# tACS_precision_revised.net
KiCad netlist of a schematic drawn in EAGLE
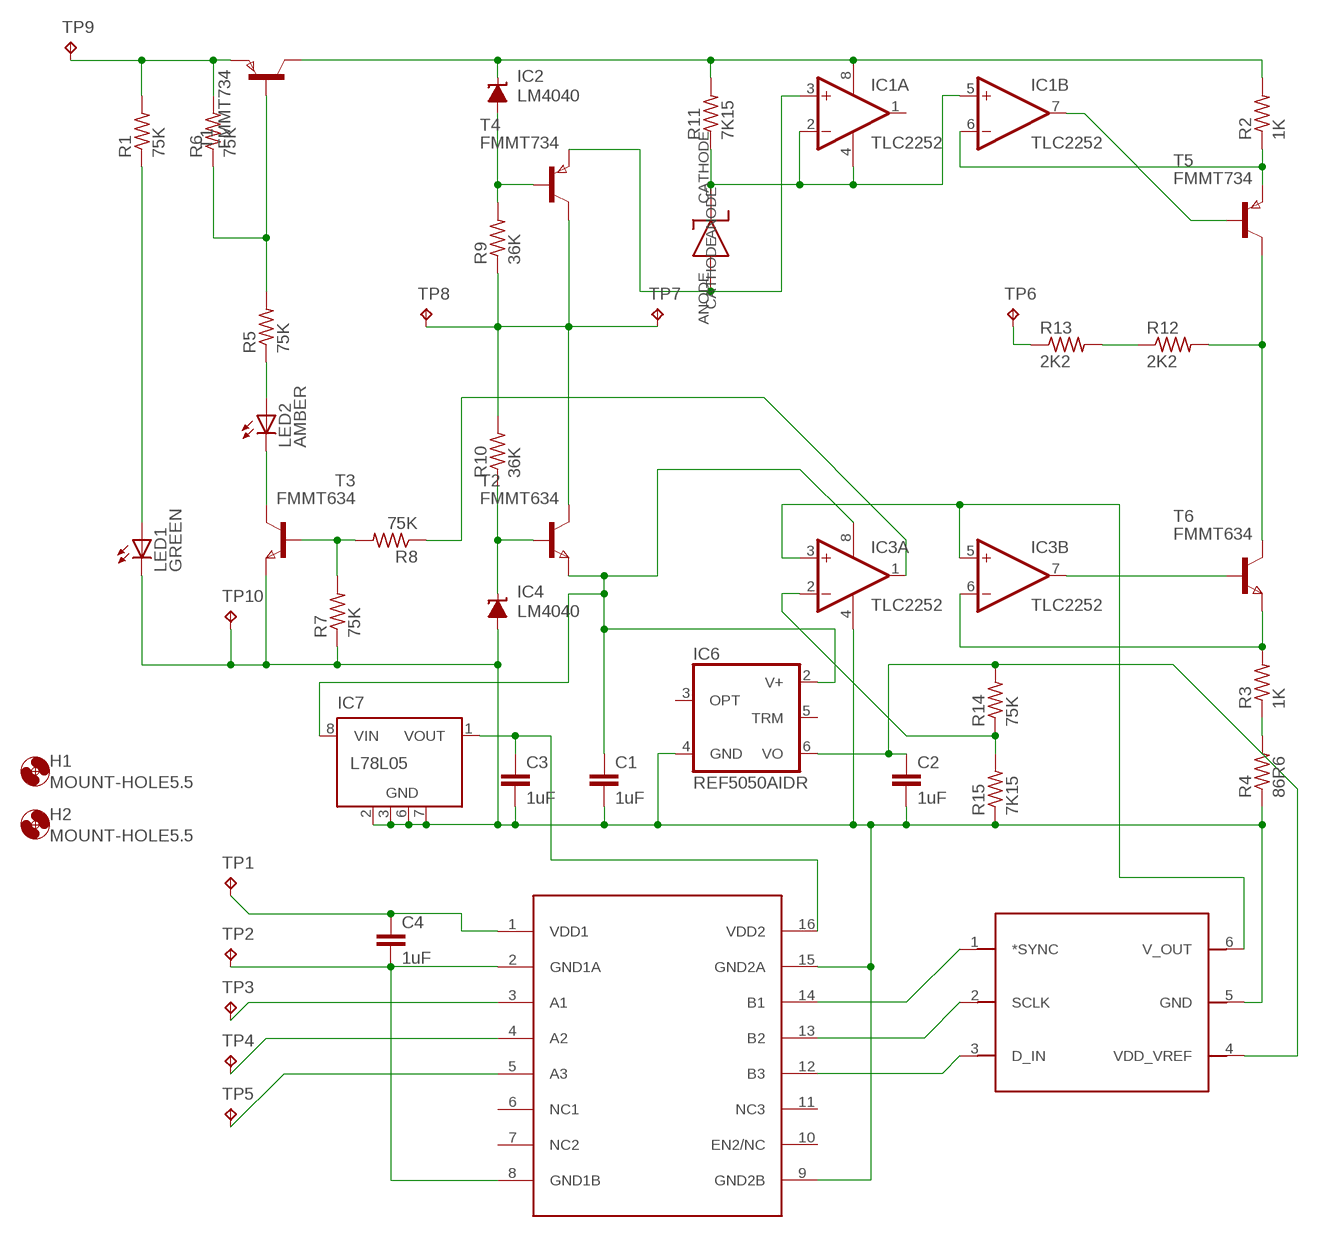
[diagram p0: schematic, sheet 1]

(export (version "E")
  (design (tool "Eeschema 10.0.6"))
  (components
    (comp (ref "C1")
      (value "1uF")
      (footprint "eagle-import:C1608")
      (libsource (lib "eagle-import") (part "C-EUC1608"))
    )
    (comp (ref "C2")
      (value "1uF")
      (footprint "eagle-import:C1608")
      (libsource (lib "eagle-import") (part "C-EUC1608"))
    )
    (comp (ref "C3")
      (value "1uF")
      (footprint "eagle-import:C1608")
      (libsource (lib "eagle-import") (part "C-EUC1608"))
    )
    (comp (ref "C4")
      (value "1uF")
      (footprint "eagle-import:C1608")
      (libsource (lib "eagle-import") (part "C-EUC1608"))
    )
    (comp (ref "H1")
      (value "MOUNT-HOLE5.5")
      (footprint "eagle-import:5,5")
      (libsource (lib "eagle-import") (part "MOUNT-HOLE5.5"))
    )
    (comp (ref "H2")
      (value "MOUNT-HOLE5.5")
      (footprint "eagle-import:5,5")
      (libsource (lib "eagle-import") (part "MOUNT-HOLE5.5"))
    )
    (comp (ref "IC1")
      (value "TLC2252")
      (footprint "eagle-import:SO08")
      (libsource (lib "eagle-import") (part "TLC272D"))
    )
    (comp (ref "IC2")
      (value "LM4040")
      (footprint "eagle-import:DBZ_R-PDSO-G3")
      (fields (field (name "MPN") "LM4041A12IDBZR"))
      (libsource (lib "eagle-import") (part "LM4041DBZA12"))
    )
    (comp (ref "IC3")
      (value "TLC2252")
      (footprint "eagle-import:SO08")
      (libsource (lib "eagle-import") (part "TLC272D"))
    )
    (comp (ref "IC4")
      (value "LM4040")
      (footprint "eagle-import:DBZ_R-PDSO-G3")
      (fields (field (name "MPN") "LM4041A12IDBZR"))
      (libsource (lib "eagle-import") (part "LM4041DBZA12"))
    )
    (comp (ref "IC6")
      (value "REF5050AIDR")
      (footprint "eagle-import:SO08")
      (libsource (lib "eagle-import") (part "REF03D"))
    )
    (comp (ref "IC7")
      (value "L78L05")
      (footprint "eagle-import:SO08")
      (libsource (lib "eagle-import") (part "78LSMD05"))
    )
    (comp (ref "LED1")
      (value "GREEN")
      (footprint "eagle-import:SML0603")
      (libsource (lib "eagle-import") (part "LEDSML0603"))
    )
    (comp (ref "LED2")
      (value "AMBER")
      (footprint "eagle-import:SML1206")
      (libsource (lib "eagle-import") (part "LEDSML1206"))
    )
    (comp (ref "R1")
      (value "75K")
      (footprint "eagle-import:R0603")
      (libsource (lib "eagle-import") (part "R-US_R0603"))
    )
    (comp (ref "R2")
      (value "1K")
      (footprint "eagle-import:R0603")
      (libsource (lib "eagle-import") (part "R-US_R0603"))
    )
    (comp (ref "R3")
      (value "1K")
      (footprint "eagle-import:R0603")
      (libsource (lib "eagle-import") (part "R-US_R0603"))
    )
    (comp (ref "R4")
      (value "86R6")
      (footprint "eagle-import:R0603")
      (libsource (lib "eagle-import") (part "R-US_R0603"))
    )
    (comp (ref "R5")
      (value "75K")
      (footprint "eagle-import:R0603")
      (libsource (lib "eagle-import") (part "R-US_R0603"))
    )
    (comp (ref "R6")
      (value "75K")
      (footprint "eagle-import:R0603")
      (libsource (lib "eagle-import") (part "R-US_R0603"))
    )
    (comp (ref "R7")
      (value "75K")
      (footprint "eagle-import:R0603")
      (libsource (lib "eagle-import") (part "R-US_R0603"))
    )
    (comp (ref "R8")
      (value "75K")
      (footprint "eagle-import:R0603")
      (libsource (lib "eagle-import") (part "R-US_R0603"))
    )
    (comp (ref "R9")
      (value "36K")
      (footprint "eagle-import:R0603")
      (libsource (lib "eagle-import") (part "R-US_R0603"))
    )
    (comp (ref "R10")
      (value "36K")
      (footprint "eagle-import:R0603")
      (libsource (lib "eagle-import") (part "R-US_R0603"))
    )
    (comp (ref "R11")
      (value "7K15")
      (footprint "eagle-import:R0603")
      (libsource (lib "eagle-import") (part "R-US_R0603"))
    )
    (comp (ref "R12")
      (value "2K2")
      (footprint "eagle-import:R2512")
      (libsource (lib "eagle-import") (part "R-US_R2512"))
    )
    (comp (ref "R13")
      (value "2K2")
      (footprint "eagle-import:R2512")
      (libsource (lib "eagle-import") (part "R-US_R2512"))
    )
    (comp (ref "R14")
      (value "75K")
      (footprint "eagle-import:R0603")
      (libsource (lib "eagle-import") (part "R-US_R0603"))
    )
    (comp (ref "R15")
      (value "7K15")
      (footprint "eagle-import:R0603")
      (libsource (lib "eagle-import") (part "R-US_R0603"))
    )
    (comp (ref "T1")
      (value "FMMT734")
      (footprint "eagle-import:SOT-23")
      (fields (field (name "MPN") "FMMT720"))
      (libsource (lib "eagle-import") (part "FMMT720"))
    )
    (comp (ref "T2")
      (value "FMMT634")
      (footprint "eagle-import:SOT-23")
      (fields (field (name "MPN") "FMMT619"))
      (libsource (lib "eagle-import") (part "FMMT624"))
    )
    (comp (ref "T3")
      (value "FMMT634")
      (footprint "eagle-import:SOT-23")
      (fields (field (name "MPN") "FMMT619"))
      (libsource (lib "eagle-import") (part "FMMT624"))
    )
    (comp (ref "T4")
      (value "FMMT734")
      (footprint "eagle-import:SOT-23")
      (fields (field (name "MPN") "FMMT720"))
      (libsource (lib "eagle-import") (part "FMMT720"))
    )
    (comp (ref "T5")
      (value "FMMT734")
      (footprint "eagle-import:SOT-23")
      (fields (field (name "MPN") "FMMT720"))
      (libsource (lib "eagle-import") (part "FMMT720"))
    )
    (comp (ref "T6")
      (value "FMMT634")
      (footprint "eagle-import:SOT-23")
      (fields (field (name "MPN") "FMMT619"))
      (libsource (lib "eagle-import") (part "FMMT624"))
    )
    (comp (ref "TP1")
      (value "TPPAD1-13Y")
      (footprint "eagle-import:P1-13Y")
      (libsource (lib "eagle-import") (part "TPPAD1-13Y"))
    )
    (comp (ref "TP2")
      (value "TPPAD1-13Y")
      (footprint "eagle-import:P1-13Y")
      (libsource (lib "eagle-import") (part "TPPAD1-13Y"))
    )
    (comp (ref "TP3")
      (value "TPPAD1-13Y")
      (footprint "eagle-import:P1-13Y")
      (libsource (lib "eagle-import") (part "TPPAD1-13Y"))
    )
    (comp (ref "TP4")
      (value "TPPAD1-13Y")
      (footprint "eagle-import:P1-13Y")
      (libsource (lib "eagle-import") (part "TPPAD1-13Y"))
    )
    (comp (ref "TP5")
      (value "TPPAD1-13Y")
      (footprint "eagle-import:P1-13Y")
      (libsource (lib "eagle-import") (part "TPPAD1-13Y"))
    )
    (comp (ref "TP6")
      (value "TPPAD1-13Y")
      (footprint "eagle-import:P1-13Y")
      (libsource (lib "eagle-import") (part "TPPAD1-13Y"))
    )
    (comp (ref "TP7")
      (value "TPPAD1-13Y")
      (footprint "eagle-import:P1-13Y")
      (libsource (lib "eagle-import") (part "TPPAD1-13Y"))
    )
    (comp (ref "TP8")
      (value "TPPAD1-13Y")
      (footprint "eagle-import:P1-13Y")
      (libsource (lib "eagle-import") (part "TPPAD1-13Y"))
    )
    (comp (ref "TP9")
      (value "TPPAD1-13Y")
      (footprint "eagle-import:P1-13Y")
      (libsource (lib "eagle-import") (part "TPPAD1-13Y"))
    )
    (comp (ref "TP10")
      (value "TPPAD1-13Y")
      (footprint "eagle-import:P1-13Y")
      (libsource (lib "eagle-import") (part "TPPAD1-13Y"))
    )
    (comp (ref "U$1")
      (value "DAC7311")
      (footprint "eagle-import:SC70-6")
      (libsource (lib "eagle-import") (part "DAC7311"))
    )
    (comp (ref "U$2")
      (value "SI8630BD")
      (footprint "eagle-import:SOIC16R")
      (libsource (lib "eagle-import") (part "SI8630BD-B-IS"))
    )
    (comp (ref "U$3")
      (value "ADR5041")
      (footprint "eagle-import:SC70-3")
      (libsource (lib "eagle-import") (part "ADR5041BKSZ"))
    )
  )
  (nets
    (net (code "1") (name "Net-(IC1A-+IN)") (class "Default")
      (node (ref "IC1") (pin "3") (pinfunction "+IN_3") (pintype "input"))
      (node (ref "T4") (pin "2") (pinfunction "E_2") (pintype "passive"))
      (node (ref "U$3") (pin "ANODE") (pinfunction "ANODE_ANODE") (pintype "bidirectional"))
    )
    (net (code "2") (name "Net-(IC1A--IN)") (class "Default")
      (node (ref "IC1") (pin "2") (pinfunction "-IN_2") (pintype "input"))
      (node (ref "IC1") (pin "4") (pinfunction "V-_4") (pintype "power_in"))
      (node (ref "IC1") (pin "5") (pinfunction "+IN_5") (pintype "input"))
      (node (ref "R11") (pin "1") (pinfunction "1_1") (pintype "passive"))
      (node (ref "U$3") (pin "CATHODE") (pinfunction "CATHODE_CATHODE") (pintype "bidirectional"))
    )
    (net (code "3") (name "Net-(IC1B--IN)") (class "Default")
      (node (ref "IC1") (pin "6") (pinfunction "-IN_6") (pintype "input"))
      (node (ref "R2") (pin "1") (pinfunction "1_1") (pintype "passive"))
      (node (ref "T5") (pin "2") (pinfunction "E_2") (pintype "passive"))
    )
    (net (code "4") (name "Net-(IC1B-OUT)") (class "Default")
      (node (ref "IC1") (pin "7") (pinfunction "OUT_7") (pintype "output"))
      (node (ref "T5") (pin "3") (pinfunction "B_3") (pintype "passive"))
    )
    (net (code "5") (name "Net-(IC1C-V+)") (class "Default")
      (node (ref "IC1") (pin "8") (pinfunction "V+_8") (pintype "power_in"))
      (node (ref "IC2") (pin "1") (pinfunction "C_1") (pintype "passive"))
      (node (ref "R11") (pin "2") (pinfunction "2_2") (pintype "passive"))
      (node (ref "R2") (pin "2") (pinfunction "2_2") (pintype "passive"))
      (node (ref "T1") (pin "1") (pinfunction "C_1") (pintype "passive"))
    )
    (net (code "6") (name "Net-(IC2-A)") (class "Default")
      (node (ref "IC2") (pin "2") (pinfunction "A_2") (pintype "passive"))
      (node (ref "R9") (pin "2") (pinfunction "2_2") (pintype "passive"))
      (node (ref "T4") (pin "3") (pinfunction "B_3") (pintype "passive"))
    )
    (net (code "7") (name "Net-(IC3A-+IN)") (class "Default")
      (node (ref "IC3") (pin "3") (pinfunction "+IN_3") (pintype "input"))
      (node (ref "IC3") (pin "5") (pinfunction "+IN_5") (pintype "input"))
      (node (ref "U$1") (pin "6") (pinfunction "V_OUT_6") (pintype "bidirectional"))
    )
    (net (code "8") (name "Net-(IC3A--IN)") (class "Default")
      (node (ref "IC3") (pin "2") (pinfunction "-IN_2") (pintype "input"))
      (node (ref "R14") (pin "1") (pinfunction "1_1") (pintype "passive"))
      (node (ref "R15") (pin "2") (pinfunction "2_2") (pintype "passive"))
    )
    (net (code "9") (name "Net-(IC3A-OUT)") (class "Default")
      (node (ref "IC3") (pin "1") (pinfunction "OUT_1") (pintype "output"))
      (node (ref "R8") (pin "1") (pinfunction "1_1") (pintype "passive"))
    )
    (net (code "10") (name "Net-(IC3B--IN)") (class "Default")
      (node (ref "IC3") (pin "6") (pinfunction "-IN_6") (pintype "input"))
      (node (ref "R3") (pin "2") (pinfunction "2_2") (pintype "passive"))
      (node (ref "T6") (pin "2") (pinfunction "E_2") (pintype "passive"))
    )
    (net (code "11") (name "Net-(IC3B-OUT)") (class "Default")
      (node (ref "IC3") (pin "7") (pinfunction "OUT_7") (pintype "output"))
      (node (ref "T6") (pin "3") (pinfunction "B_3") (pintype "passive"))
    )
    (net (code "12") (name "Net-(IC3C-V+)") (class "Default")
      (node (ref "C1") (pin "1") (pinfunction "1_1") (pintype "passive"))
      (node (ref "IC3") (pin "8") (pinfunction "V+_8") (pintype "power_in"))
      (node (ref "IC6") (pin "2") (pinfunction "V+_2") (pintype "power_in"))
      (node (ref "IC7") (pin "8") (pinfunction "VIN_8") (pintype "passive"))
      (node (ref "T2") (pin "2") (pinfunction "E_2") (pintype "passive"))
    )
    (net (code "13") (name "Net-(IC3C-V-)") (class "Default")
      (node (ref "C1") (pin "2") (pinfunction "2_2") (pintype "passive"))
      (node (ref "C2") (pin "2") (pinfunction "2_2") (pintype "passive"))
      (node (ref "C3") (pin "2") (pinfunction "2_2") (pintype "passive"))
      (node (ref "IC3") (pin "4") (pinfunction "V-_4") (pintype "power_in"))
      (node (ref "IC4") (pin "2") (pinfunction "A_2") (pintype "passive"))
      (node (ref "IC6") (pin "4") (pinfunction "GND_4") (pintype "power_in"))
      (node (ref "IC7") (pin "2") (pinfunction "GND_2") (pintype "power_in"))
      (node (ref "IC7") (pin "3") (pinfunction "GND_3") (pintype "power_in"))
      (node (ref "IC7") (pin "6") (pinfunction "GND_6") (pintype "power_in"))
      (node (ref "IC7") (pin "7") (pinfunction "GND_7") (pintype "power_in"))
      (node (ref "LED1") (pin "C") (pinfunction "C_C") (pintype "passive"))
      (node (ref "R15") (pin "1") (pinfunction "1_1") (pintype "passive"))
      (node (ref "R4") (pin "1") (pinfunction "1_1") (pintype "passive"))
      (node (ref "R7") (pin "1") (pinfunction "1_1") (pintype "passive"))
      (node (ref "T3") (pin "2") (pinfunction "E_2") (pintype "passive"))
      (node (ref "TP10") (pin "TP") (pinfunction "TP_TP") (pintype "input"))
      (node (ref "U$1") (pin "5") (pinfunction "GND_5") (pintype "bidirectional"))
      (node (ref "U$2") (pin "15") (pinfunction "GND2A_15") (pintype "bidirectional"))
      (node (ref "U$2") (pin "9") (pinfunction "GND2B_9") (pintype "bidirectional"))
    )
    (net (code "14") (name "Net-(IC4-C)") (class "Default")
      (node (ref "IC4") (pin "1") (pinfunction "C_1") (pintype "passive"))
      (node (ref "R10") (pin "1") (pinfunction "1_1") (pintype "passive"))
      (node (ref "T2") (pin "3") (pinfunction "B_3") (pintype "passive"))
    )
    (net (code "15") (name "Net-(IC6-VO)") (class "Default")
      (node (ref "C2") (pin "1") (pinfunction "1_1") (pintype "passive"))
      (node (ref "IC6") (pin "6") (pinfunction "VO_6") (pintype "output"))
      (node (ref "R14") (pin "2") (pinfunction "2_2") (pintype "passive"))
      (node (ref "U$1") (pin "4") (pinfunction "VDD_VREF_4") (pintype "bidirectional"))
    )
    (net (code "16") (name "Net-(IC7A-VOUT)") (class "Default")
      (node (ref "C3") (pin "1") (pinfunction "1_1") (pintype "passive"))
      (node (ref "IC7") (pin "1") (pinfunction "VOUT_1") (pintype "output"))
      (node (ref "U$2") (pin "16") (pinfunction "VDD2_16") (pintype "bidirectional"))
    )
    (net (code "17") (name "Net-(LED1-PadA)") (class "Default")
      (node (ref "LED1") (pin "A") (pinfunction "A_A") (pintype "passive"))
      (node (ref "R1") (pin "1") (pinfunction "1_1") (pintype "passive"))
    )
    (net (code "18") (name "Net-(LED2-PadA)") (class "Default")
      (node (ref "LED2") (pin "A") (pinfunction "A_A") (pintype "passive"))
      (node (ref "R5") (pin "1") (pinfunction "1_1") (pintype "passive"))
    )
    (net (code "19") (name "Net-(R3-Pad1)") (class "Default")
      (node (ref "R3") (pin "1") (pinfunction "1_1") (pintype "passive"))
      (node (ref "R4") (pin "2") (pinfunction "2_2") (pintype "passive"))
    )
    (net (code "20") (name "Net-(R12-Pad1)") (class "Default")
      (node (ref "R12") (pin "1") (pinfunction "1_1") (pintype "passive"))
      (node (ref "R13") (pin "2") (pinfunction "2_2") (pintype "passive"))
    )
    (net (code "21") (name "Net-(R13-Pad1)") (class "Default")
      (node (ref "R13") (pin "1") (pinfunction "1_1") (pintype "passive"))
      (node (ref "TP6") (pin "TP") (pinfunction "TP_TP") (pintype "input"))
    )
    (net (code "22") (name "Net-(T1-B)") (class "Default")
      (node (ref "R5") (pin "2") (pinfunction "2_2") (pintype "passive"))
      (node (ref "R6") (pin "1") (pinfunction "1_1") (pintype "passive"))
      (node (ref "T1") (pin "3") (pinfunction "B_3") (pintype "passive"))
    )
    (net (code "23") (name "Net-(T1-E)") (class "Default")
      (node (ref "R1") (pin "2") (pinfunction "2_2") (pintype "passive"))
      (node (ref "R6") (pin "2") (pinfunction "2_2") (pintype "passive"))
      (node (ref "T1") (pin "2") (pinfunction "E_2") (pintype "passive"))
      (node (ref "TP9") (pin "TP") (pinfunction "TP_TP") (pintype "input"))
    )
    (net (code "24") (name "Net-(T2-C)") (class "Default")
      (node (ref "R10") (pin "2") (pinfunction "2_2") (pintype "passive"))
      (node (ref "R9") (pin "1") (pinfunction "1_1") (pintype "passive"))
      (node (ref "T2") (pin "1") (pinfunction "C_1") (pintype "passive"))
      (node (ref "T4") (pin "1") (pinfunction "C_1") (pintype "passive"))
      (node (ref "TP7") (pin "TP") (pinfunction "TP_TP") (pintype "input"))
      (node (ref "TP8") (pin "TP") (pinfunction "TP_TP") (pintype "input"))
    )
    (net (code "25") (name "Net-(T3-B)") (class "Default")
      (node (ref "R7") (pin "2") (pinfunction "2_2") (pintype "passive"))
      (node (ref "R8") (pin "2") (pinfunction "2_2") (pintype "passive"))
      (node (ref "T3") (pin "3") (pinfunction "B_3") (pintype "passive"))
    )
    (net (code "26") (name "Net-(T3-C)") (class "Default")
      (node (ref "LED2") (pin "C") (pinfunction "C_C") (pintype "passive"))
      (node (ref "T3") (pin "1") (pinfunction "C_1") (pintype "passive"))
    )
    (net (code "27") (name "Net-(T5-C)") (class "Default")
      (node (ref "R12") (pin "2") (pinfunction "2_2") (pintype "passive"))
      (node (ref "T5") (pin "1") (pinfunction "C_1") (pintype "passive"))
      (node (ref "T6") (pin "1") (pinfunction "C_1") (pintype "passive"))
    )
    (net (code "28") (name "Net-(U$1-*SYNC)") (class "Default")
      (node (ref "U$1") (pin "1") (pinfunction "*SYNC_1") (pintype "bidirectional"))
      (node (ref "U$2") (pin "14") (pinfunction "B1_14") (pintype "bidirectional"))
    )
    (net (code "29") (name "Net-(U$1-D_IN)") (class "Default")
      (node (ref "U$1") (pin "3") (pinfunction "D_IN_3") (pintype "bidirectional"))
      (node (ref "U$2") (pin "12") (pinfunction "B3_12") (pintype "bidirectional"))
    )
    (net (code "30") (name "Net-(U$1-SCLK)") (class "Default")
      (node (ref "U$1") (pin "2") (pinfunction "SCLK_2") (pintype "bidirectional"))
      (node (ref "U$2") (pin "13") (pinfunction "B2_13") (pintype "bidirectional"))
    )
    (net (code "31") (name "Net-(U$2-A1)") (class "Default")
      (node (ref "TP3") (pin "TP") (pinfunction "TP_TP") (pintype "input"))
      (node (ref "U$2") (pin "3") (pinfunction "A1_3") (pintype "bidirectional"))
    )
    (net (code "32") (name "Net-(U$2-A2)") (class "Default")
      (node (ref "TP4") (pin "TP") (pinfunction "TP_TP") (pintype "input"))
      (node (ref "U$2") (pin "4") (pinfunction "A2_4") (pintype "bidirectional"))
    )
    (net (code "33") (name "Net-(U$2-A3)") (class "Default")
      (node (ref "TP5") (pin "TP") (pinfunction "TP_TP") (pintype "input"))
      (node (ref "U$2") (pin "5") (pinfunction "A3_5") (pintype "bidirectional"))
    )
    (net (code "34") (name "Net-(U$2-GND1A)") (class "Default")
      (node (ref "C4") (pin "2") (pinfunction "2_2") (pintype "passive"))
      (node (ref "TP2") (pin "TP") (pinfunction "TP_TP") (pintype "input"))
      (node (ref "U$2") (pin "2") (pinfunction "GND1A_2") (pintype "bidirectional"))
      (node (ref "U$2") (pin "8") (pinfunction "GND1B_8") (pintype "bidirectional"))
    )
    (net (code "35") (name "Net-(U$2-VDD1)") (class "Default")
      (node (ref "C4") (pin "1") (pinfunction "1_1") (pintype "passive"))
      (node (ref "TP1") (pin "TP") (pinfunction "TP_TP") (pintype "input"))
      (node (ref "U$2") (pin "1") (pinfunction "VDD1_1") (pintype "bidirectional"))
    )
    (net (code "36") (name "unconnected-(IC1A-OUT-Pad1)") (class "Default")
      (node (ref "IC1") (pin "1") (pinfunction "OUT_1") (pintype "output"))
    )
    (net (code "37") (name "unconnected-(IC6-OPT-Pad3)") (class "Default")
      (node (ref "IC6") (pin "3") (pinfunction "OPT_3") (pintype "output"))
    )
    (net (code "38") (name "unconnected-(IC6-TRM-Pad5)") (class "Default")
      (node (ref "IC6") (pin "5") (pinfunction "TRM_5") (pintype "input"))
    )
    (net (code "39") (name "unconnected-(U$2-EN2{slash}NC-Pad10)") (class "Default")
      (node (ref "U$2") (pin "10") (pinfunction "EN2/NC_10") (pintype "bidirectional"))
    )
    (net (code "40") (name "unconnected-(U$2-NC1-Pad6)") (class "Default")
      (node (ref "U$2") (pin "6") (pinfunction "NC1_6") (pintype "bidirectional"))
    )
    (net (code "41") (name "unconnected-(U$2-NC2-Pad7)") (class "Default")
      (node (ref "U$2") (pin "7") (pinfunction "NC2_7") (pintype "bidirectional"))
    )
    (net (code "42") (name "unconnected-(U$2-NC3-Pad11)") (class "Default")
      (node (ref "U$2") (pin "11") (pinfunction "NC3_11") (pintype "bidirectional"))
    )
  )
)
